# sensor_board.net
KiCad netlist of a schematic drawn in EAGLE
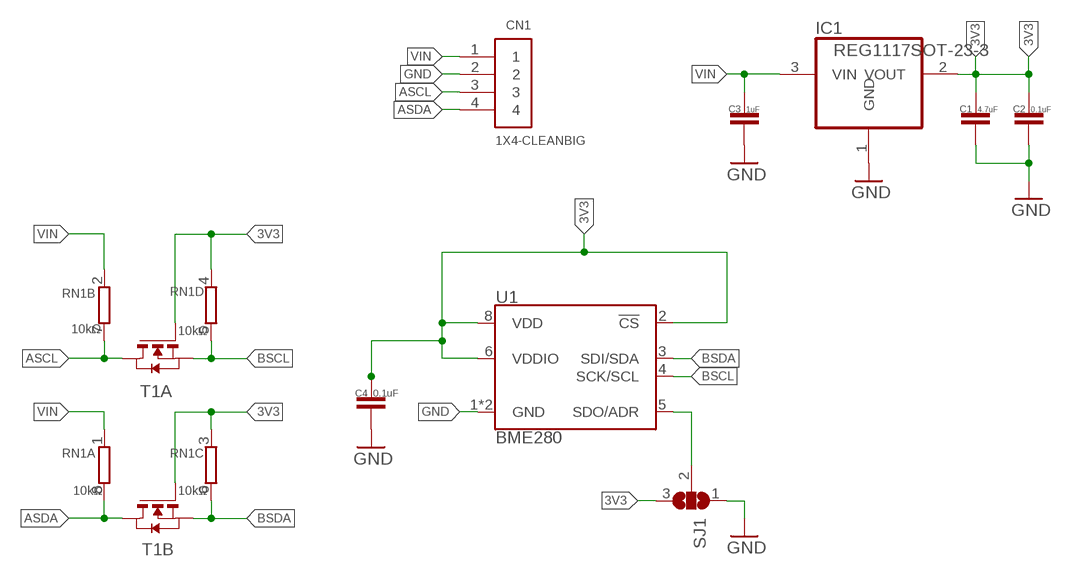
[diagram p0: schematic, sheet 1]

(export (version "E")
  (design (tool "Eeschema 10.0.6"))
  (components
    (comp (ref "C1")
      (value "4.7uF")
      (footprint "eagle-import:C0603")
      (libsource (lib "eagle-import") (part "C-EUC0603"))
    )
    (comp (ref "C2")
      (value "0.1uF")
      (footprint "eagle-import:C0603")
      (libsource (lib "eagle-import") (part "C-EUC0603"))
    )
    (comp (ref "C3")
      (value "1uF")
      (footprint "eagle-import:C0603")
      (libsource (lib "eagle-import") (part "C-EUC0603"))
    )
    (comp (ref "C4")
      (value "0.1uF")
      (footprint "eagle-import:C0603")
      (libsource (lib "eagle-import") (part "C-EUC0603"))
    )
    (comp (ref "CN1")
      (value "1X4-CLEANBIG")
      (footprint "eagle-import:1X04-CLEANBIG")
      (libsource (lib "eagle-import") (part "1X4-CLEANBIG"))
    )
    (comp (ref "IC1")
      (value "REG1117SOT-23-3")
      (footprint "eagle-import:SOT23-3")
      (libsource (lib "eagle-import") (part "REG1117SOT-23-3"))
    )
    (comp (ref "RN1")
      (value "10kΩ")
      (footprint "eagle-import:EXB38V")
      (libsource (lib "eagle-import") (part "4R-NEXB38V"))
    )
    (comp (ref "SJ1")
      (value "SJ2W")
      (footprint "eagle-import:SJ_2")
      (libsource (lib "eagle-import") (part "SJ2W"))
    )
    (comp (ref "T1")
      (value "ZXMD63N03XSOT-363")
      (footprint "eagle-import:SOT-363")
      (libsource (lib "eagle-import") (part "ZXMD63N03XSOT-363"))
    )
    (comp (ref "U1")
      (value "BME280")
      (footprint "eagle-import:LGA-8-2.5X2.5")
      (libsource (lib "eagle-import") (part "BME280"))
    )
  )
  (nets
    (net (code "1") (name "3V3") (class "Default")
      (node (ref "C1") (pin "1") (pinfunction "1_1") (pintype "passive"))
      (node (ref "C2") (pin "1") (pinfunction "1_1") (pintype "passive"))
      (node (ref "C4") (pin "1") (pinfunction "1_1") (pintype "passive"))
      (node (ref "IC1") (pin "2") (pinfunction "VOUT_2") (pintype "output"))
      (node (ref "RN1") (pin "3") (pinfunction "1_3") (pintype "passive"))
      (node (ref "RN1") (pin "4") (pinfunction "1_4") (pintype "passive"))
      (node (ref "SJ1") (pin "3") (pinfunction "3_3") (pintype "passive"))
      (node (ref "T1") (pin "2") (pinfunction "G_2") (pintype "passive"))
      (node (ref "T1") (pin "5") (pinfunction "G_5") (pintype "passive"))
      (node (ref "U1") (pin "2") (pinfunction "~{CS}_2") (pintype "bidirectional"))
      (node (ref "U1") (pin "6") (pinfunction "VDDIO_6") (pintype "bidirectional"))
      (node (ref "U1") (pin "8") (pinfunction "VDD_8") (pintype "bidirectional"))
    )
    (net (code "2") (name "ASCL") (class "Default")
      (node (ref "CN1") (pin "3") (pinfunction "3_3") (pintype "bidirectional"))
      (node (ref "RN1") (pin "7") (pinfunction "2_7") (pintype "passive"))
      (node (ref "T1") (pin "6") (pinfunction "D_6") (pintype "passive"))
    )
    (net (code "3") (name "ASDA") (class "Default")
      (node (ref "CN1") (pin "4") (pinfunction "4_4") (pintype "bidirectional"))
      (node (ref "RN1") (pin "8") (pinfunction "2_8") (pintype "passive"))
      (node (ref "T1") (pin "3") (pinfunction "D_3") (pintype "passive"))
    )
    (net (code "4") (name "BSCL") (class "Default")
      (node (ref "RN1") (pin "5") (pinfunction "2_5") (pintype "passive"))
      (node (ref "T1") (pin "1") (pinfunction "S_1") (pintype "passive"))
      (node (ref "U1") (pin "4") (pinfunction "SCK/SCL_4") (pintype "bidirectional"))
    )
    (net (code "5") (name "BSDA") (class "Default")
      (node (ref "RN1") (pin "6") (pinfunction "2_6") (pintype "passive"))
      (node (ref "T1") (pin "4") (pinfunction "S_4") (pintype "passive"))
      (node (ref "U1") (pin "3") (pinfunction "SDI/SDA_3") (pintype "bidirectional"))
    )
    (net (code "6") (name "GND") (class "Default")
      (node (ref "C1") (pin "2") (pinfunction "2_2") (pintype "passive"))
      (node (ref "C2") (pin "2") (pinfunction "2_2") (pintype "passive"))
      (node (ref "C3") (pin "2") (pinfunction "2_2") (pintype "passive"))
      (node (ref "C4") (pin "2") (pinfunction "2_2") (pintype "passive"))
      (node (ref "CN1") (pin "2") (pinfunction "2_2") (pintype "bidirectional"))
      (node (ref "IC1") (pin "1") (pinfunction "GND_1") (pintype "power_in"))
      (node (ref "SJ1") (pin "1") (pinfunction "1_1") (pintype "passive"))
      (node (ref "U1") (pin "1") (pinfunction "GND_1") (pintype "bidirectional"))
      (node (ref "U1") (pin "7") (pinfunction "GND_7") (pintype "bidirectional"))
    )
    (net (code "7") (name "Net-(U1-SDO{slash}ADR)") (class "Default")
      (node (ref "SJ1") (pin "2") (pinfunction "2_2") (pintype "passive"))
      (node (ref "U1") (pin "5") (pinfunction "SDO/ADR_5") (pintype "bidirectional"))
    )
    (net (code "8") (name "VIN") (class "Default")
      (node (ref "C3") (pin "1") (pinfunction "1_1") (pintype "passive"))
      (node (ref "CN1") (pin "1") (pinfunction "1_1") (pintype "bidirectional"))
      (node (ref "IC1") (pin "3") (pinfunction "VIN_3") (pintype "input"))
      (node (ref "RN1") (pin "1") (pinfunction "1_1") (pintype "passive"))
      (node (ref "RN1") (pin "2") (pinfunction "1_2") (pintype "passive"))
    )
  )
)
